# Rauchmelder_2_2A.net
KiCad netlist of a schematic drawn in EAGLE
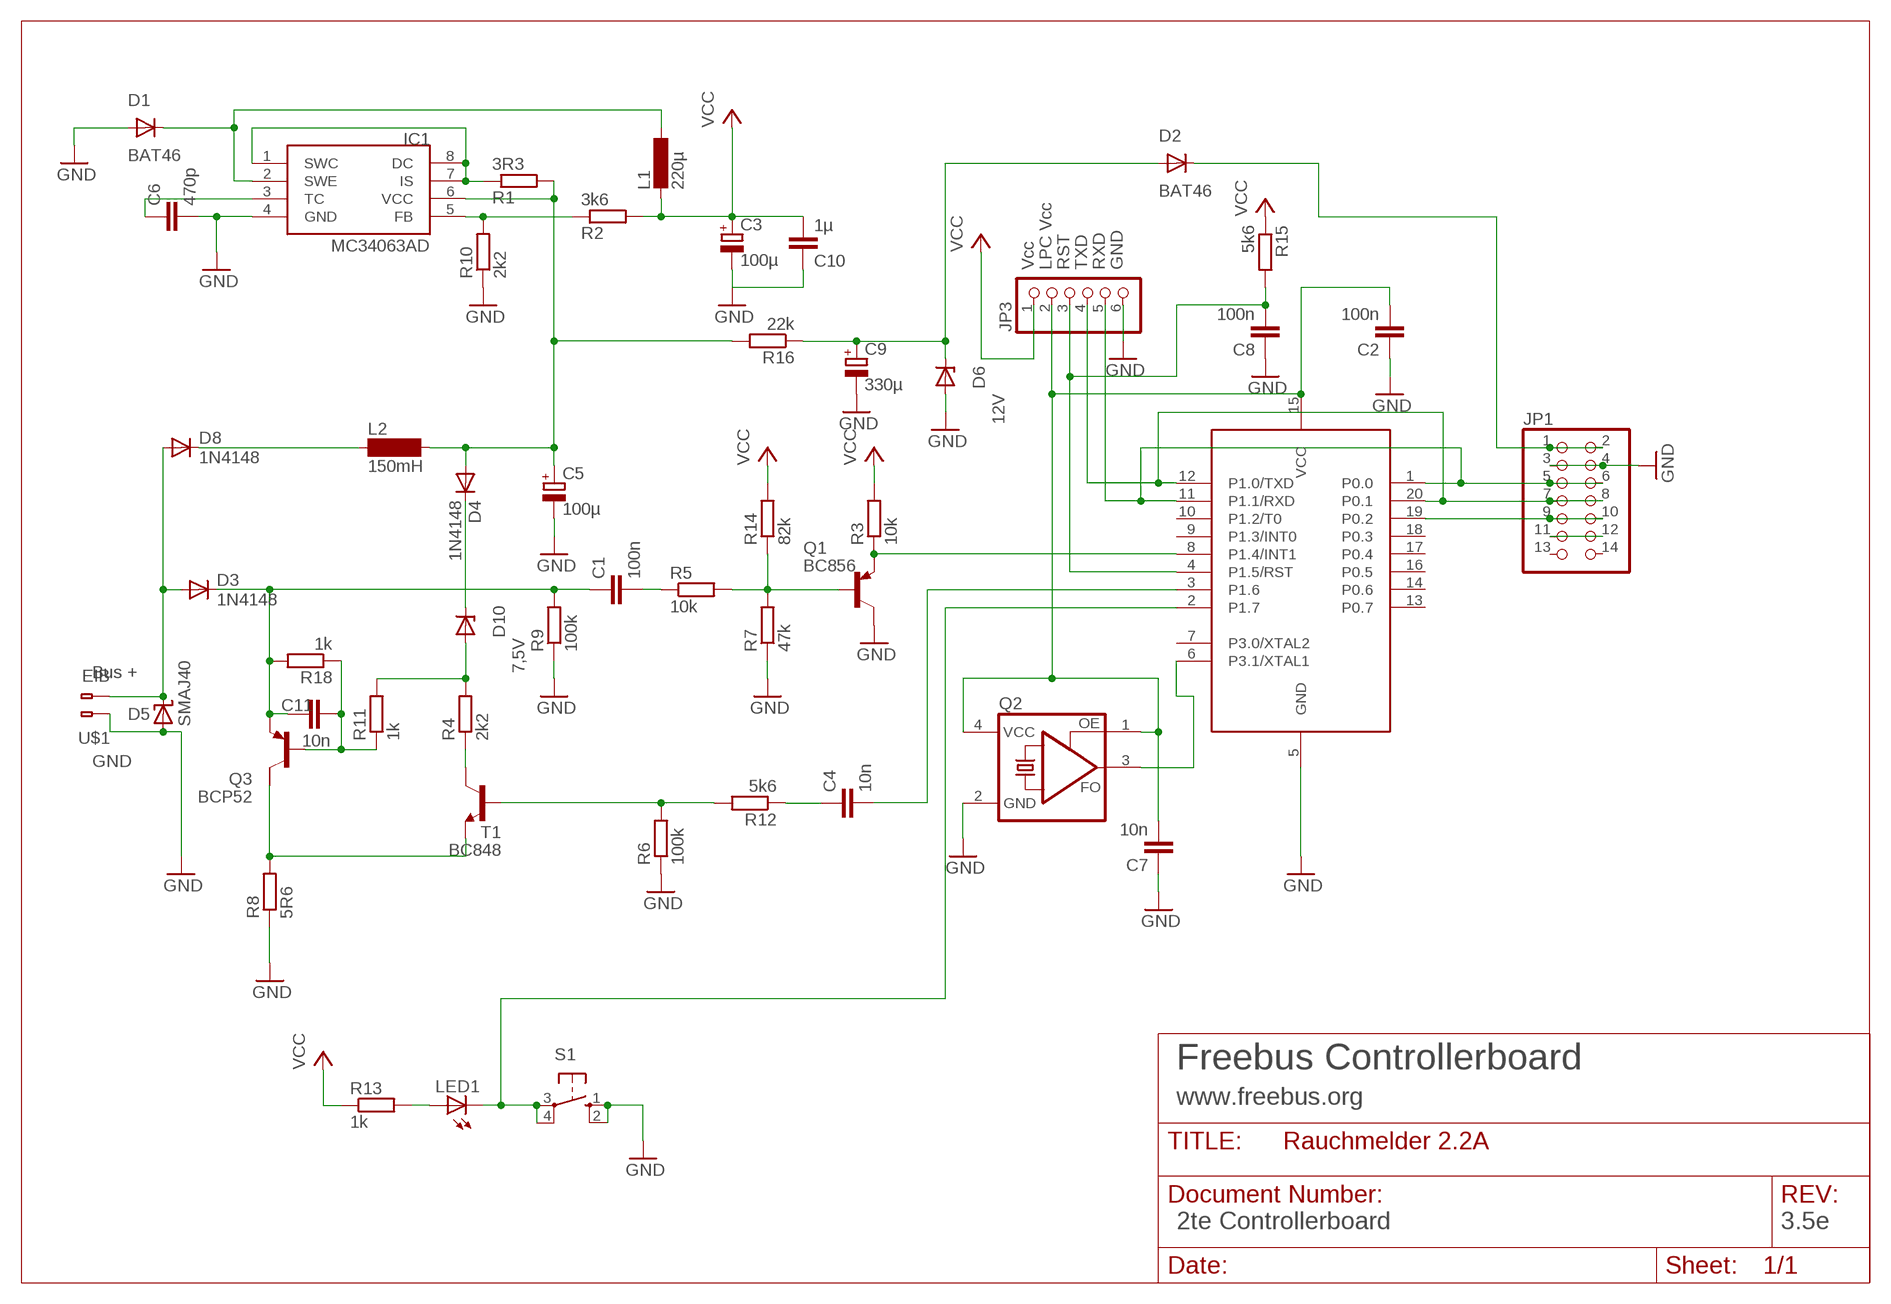
[diagram p0: schematic, sheet 1]

(export (version "E")
  (design (tool "Eeschema 10.0.6"))
  (components
    (comp (ref "C1")
      (value "100n")
      (footprint "eagle-import:C1206")
      (libsource (lib "eagle-import") (part "C-EUC1206"))
    )
    (comp (ref "C2")
      (value "100n")
      (footprint "eagle-import:C1206")
      (libsource (lib "eagle-import") (part "C-EUC1206"))
    )
    (comp (ref "C3")
      (value "100µ")
      (footprint "eagle-import:SANYO-OSCON_SMD_B6")
      (libsource (lib "eagle-import") (part "CPOL-EUSANYO_SMD_B6"))
    )
    (comp (ref "C4")
      (value "10n")
      (footprint "eagle-import:C1206")
      (libsource (lib "eagle-import") (part "C-EUC1206"))
    )
    (comp (ref "C5")
      (value "100µ")
      (footprint "eagle-import:SANYO-OSCON_SMD_C6")
      (libsource (lib "eagle-import") (part "CPOL-EUSANYO_SMD_C6"))
    )
    (comp (ref "C6")
      (value "470p")
      (footprint "eagle-import:C1206")
      (libsource (lib "eagle-import") (part "C-EUC1206"))
    )
    (comp (ref "C7")
      (value "10n")
      (footprint "eagle-import:C1206")
      (libsource (lib "eagle-import") (part "C-EUC1206"))
    )
    (comp (ref "C8")
      (value "100n")
      (footprint "eagle-import:C1206")
      (libsource (lib "eagle-import") (part "C-EUC1206"))
    )
    (comp (ref "C9")
      (value "330µ")
      (footprint "eagle-import:E3,5-8")
      (libsource (lib "eagle-import") (part "CPOL-EUE3.5-8"))
    )
    (comp (ref "C10")
      (value "1µ")
      (footprint "eagle-import:C1206")
      (libsource (lib "eagle-import") (part "C-EUC1206"))
    )
    (comp (ref "C11")
      (value "10n")
      (footprint "eagle-import:C1206")
      (libsource (lib "eagle-import") (part "C-EUC1206"))
    )
    (comp (ref "D1")
      (value "BAT46")
      (footprint "eagle-import:MINIMELF")
      (libsource (lib "eagle-import") (part "DIODE-MINIMELF"))
    )
    (comp (ref "D2")
      (value "BAT46")
      (footprint "eagle-import:MINIMELF")
      (libsource (lib "eagle-import") (part "DIODE-MINIMELF"))
    )
    (comp (ref "D3")
      (value "1N4148")
      (footprint "eagle-import:MINIMELF")
      (libsource (lib "eagle-import") (part "DIODE-MINIMELF"))
    )
    (comp (ref "D4")
      (value "1N4148")
      (footprint "eagle-import:MINIMELF")
      (libsource (lib "eagle-import") (part "DIODE-MINIMELF"))
    )
    (comp (ref "D5")
      (value "SMAJ40")
      (footprint "eagle-import:SMBJ")
      (libsource (lib "eagle-import") (part "SUPPRESSOR-SMBJ"))
    )
    (comp (ref "D6")
      (value "12V")
      (footprint "eagle-import:MINIMELF")
      (libsource (lib "eagle-import") (part "ZPD"))
    )
    (comp (ref "D8")
      (value "1N4148")
      (footprint "eagle-import:MINIMELF")
      (libsource (lib "eagle-import") (part "DIODE-MINIMELF"))
    )
    (comp (ref "D10")
      (value "7,5V")
      (footprint "eagle-import:MINIMELF")
      (libsource (lib "eagle-import") (part "ZPD"))
    )
    (comp (ref "IC1")
      (value "MC34063AD")
      (footprint "eagle-import:SOIC8")
      (libsource (lib "eagle-import") (part "MC34063AD"))
    )
    (comp (ref "IC3")
      (value "LPC922FDH")
      (footprint "eagle-import:TSSOP20")
      (libsource (lib "eagle-import") (part "LPC922FDH"))
    )
    (comp (ref "JP1")
      (value "PINHD-2X7")
      (footprint "eagle-import:2X07")
      (libsource (lib "eagle-import") (part "PINHD-2X7"))
    )
    (comp (ref "JP3")
      (value "PINHD-1X6")
      (footprint "eagle-import:1X06")
      (libsource (lib "eagle-import") (part "PINHD-1X6"))
    )
    (comp (ref "L1")
      (value "220µ")
      (footprint "eagle-import:0207_10")
      (libsource (lib "eagle-import") (part "L-EU0207/10"))
    )
    (comp (ref "L2")
      (value "150mH")
      (footprint "eagle-import:BS11")
      (libsource (lib "eagle-import") (part "BS11"))
    )
    (comp (ref "LED1")
      (value "LED3MM")
      (footprint "eagle-import:LED3MM")
      (libsource (lib "eagle-import") (part "LED3MM"))
    )
    (comp (ref "Q1")
      (value "BC856")
      (footprint "eagle-import:SOT23-BEC")
      (libsource (lib "eagle-import") (part "BC856SMDALT1"))
    )
    (comp (ref "Q2")
      (value "ASFL")
      (footprint "eagle-import:ASF")
      (libsource (lib "eagle-import") (part "ASFL"))
    )
    (comp (ref "Q3")
      (value "BCP52")
      (footprint "eagle-import:SOT223")
      (libsource (lib "eagle-import") (part "FZT753SMD"))
    )
    (comp (ref "R1")
      (value "3R3")
      (footprint "eagle-import:R1206")
      (libsource (lib "eagle-import") (part "R-EU_R1206"))
    )
    (comp (ref "R2")
      (value "3k6")
      (footprint "eagle-import:R1206")
      (libsource (lib "eagle-import") (part "R-EU_R1206"))
    )
    (comp (ref "R3")
      (value "10k")
      (footprint "eagle-import:R1206")
      (libsource (lib "eagle-import") (part "R-EU_R1206"))
    )
    (comp (ref "R4")
      (value "2k2")
      (footprint "eagle-import:R1206")
      (libsource (lib "eagle-import") (part "R-EU_R1206"))
    )
    (comp (ref "R5")
      (value "10k")
      (footprint "eagle-import:R1206")
      (libsource (lib "eagle-import") (part "R-EU_R1206"))
    )
    (comp (ref "R6")
      (value "100k")
      (footprint "eagle-import:R1206")
      (libsource (lib "eagle-import") (part "R-EU_R1206"))
    )
    (comp (ref "R7")
      (value "47k")
      (footprint "eagle-import:R1206")
      (libsource (lib "eagle-import") (part "R-EU_R1206"))
    )
    (comp (ref "R8")
      (value "5R6")
      (footprint "eagle-import:R1206")
      (libsource (lib "eagle-import") (part "R-EU_R1206"))
    )
    (comp (ref "R9")
      (value "100k")
      (footprint "eagle-import:R1206")
      (libsource (lib "eagle-import") (part "R-EU_R1206"))
    )
    (comp (ref "R10")
      (value "2k2")
      (footprint "eagle-import:R1206")
      (libsource (lib "eagle-import") (part "R-EU_R1206"))
    )
    (comp (ref "R11")
      (value "1k")
      (footprint "eagle-import:R1206")
      (libsource (lib "eagle-import") (part "R-EU_R1206"))
    )
    (comp (ref "R12")
      (value "5k6")
      (footprint "eagle-import:R1206")
      (libsource (lib "eagle-import") (part "R-EU_R1206"))
    )
    (comp (ref "R13")
      (value "1k")
      (footprint "eagle-import:R1206")
      (libsource (lib "eagle-import") (part "R-EU_R1206"))
    )
    (comp (ref "R14")
      (value "82k")
      (footprint "eagle-import:R1206")
      (libsource (lib "eagle-import") (part "R-EU_R1206"))
    )
    (comp (ref "R15")
      (value "5k6")
      (footprint "eagle-import:R1206")
      (libsource (lib "eagle-import") (part "R-EU_R1206"))
    )
    (comp (ref "R16")
      (value "22k")
      (footprint "eagle-import:R1206")
      (libsource (lib "eagle-import") (part "R-EU_R1206"))
    )
    (comp (ref "R18")
      (value "1k")
      (footprint "eagle-import:R1206")
      (libsource (lib "eagle-import") (part "R-EU_R1206"))
    )
    (comp (ref "S1")
      (value "10-XX")
      (footprint "eagle-import:B3F-10XX")
      (libsource (lib "eagle-import") (part "10-XX"))
    )
    (comp (ref "T1")
      (value "BC848")
      (footprint "eagle-import:SOT23")
      (libsource (lib "eagle-import") (part "BC848"))
    )
    (comp (ref "U$1")
      (value "EIB")
      (footprint "eagle-import:BUSKLEMME243-724")
      (libsource (lib "eagle-import") (part "EIB"))
    )
  )
  (nets
    (net (code "1") (name "GND") (class "Default")
      (node (ref "C10") (pin "1") (pinfunction "1_1") (pintype "passive"))
      (node (ref "C2") (pin "1") (pinfunction "1_1") (pintype "passive"))
      (node (ref "C3") (pin "-") (pinfunction "-_-") (pintype "passive"))
      (node (ref "C5") (pin "-") (pinfunction "-_-") (pintype "passive"))
      (node (ref "C6") (pin "2") (pinfunction "2_2") (pintype "passive"))
      (node (ref "C7") (pin "1") (pinfunction "1_1") (pintype "passive"))
      (node (ref "C8") (pin "1") (pinfunction "1_1") (pintype "passive"))
      (node (ref "C9") (pin "-") (pinfunction "-_-") (pintype "passive"))
      (node (ref "D1") (pin "A") (pinfunction "A_A") (pintype "passive"))
      (node (ref "D5") (pin "A") (pinfunction "A_A") (pintype "passive"))
      (node (ref "D6") (pin "A") (pinfunction "A_A") (pintype "passive"))
      (node (ref "IC1") (pin "4") (pinfunction "GND_4") (pintype "passive"))
      (node (ref "IC3") (pin "5") (pinfunction "GND_5") (pintype "bidirectional"))
      (node (ref "JP1") (pin "3") (pinfunction "3_3") (pintype "passive"))
      (node (ref "JP1") (pin "4") (pinfunction "4_4") (pintype "passive"))
      (node (ref "JP3") (pin "6") (pinfunction "6_6") (pintype "passive"))
      (node (ref "Q1") (pin "C") (pinfunction "C_C") (pintype "passive"))
      (node (ref "Q2") (pin "2") (pinfunction "GND_2") (pintype "power_in"))
      (node (ref "R10") (pin "1") (pinfunction "1_1") (pintype "passive"))
      (node (ref "R6") (pin "1") (pinfunction "1_1") (pintype "passive"))
      (node (ref "R7") (pin "1") (pinfunction "1_1") (pintype "passive"))
      (node (ref "R8") (pin "1") (pinfunction "1_1") (pintype "passive"))
      (node (ref "R9") (pin "1") (pinfunction "1_1") (pintype "passive"))
      (node (ref "S1") (pin "1") (pinfunction "S_1") (pintype "passive"))
      (node (ref "S1") (pin "2") (pinfunction "S1_2") (pintype "passive"))
      (node (ref "U$1") (pin "1") (pinfunction "B-1_1") (pintype "passive"))
    )
    (net (code "2") (name "Net-(C1-Pad2)") (class "Default")
      (node (ref "C1") (pin "2") (pinfunction "2_2") (pintype "passive"))
      (node (ref "R5") (pin "1") (pinfunction "1_1") (pintype "passive"))
    )
    (net (code "3") (name "Net-(C4-Pad1)") (class "Default")
      (node (ref "C4") (pin "1") (pinfunction "1_1") (pintype "passive"))
      (node (ref "R12") (pin "1") (pinfunction "1_1") (pintype "passive"))
    )
    (net (code "4") (name "Net-(C9-Pad+)") (class "Default")
      (node (ref "C9") (pin "+") (pinfunction "+_+") (pintype "passive"))
      (node (ref "D2") (pin "A") (pinfunction "A_A") (pintype "passive"))
      (node (ref "D6") (pin "C") (pinfunction "C_C") (pintype "passive"))
      (node (ref "R16") (pin "1") (pinfunction "1_1") (pintype "passive"))
    )
    (net (code "5") (name "Net-(D2-PadC)") (class "Default")
      (node (ref "D2") (pin "C") (pinfunction "C_C") (pintype "passive"))
      (node (ref "JP1") (pin "1") (pinfunction "1_1") (pintype "passive"))
      (node (ref "JP1") (pin "2") (pinfunction "2_2") (pintype "passive"))
    )
    (net (code "6") (name "Net-(D8-PadC)") (class "Default")
      (node (ref "D8") (pin "C") (pinfunction "C_C") (pintype "passive"))
      (node (ref "L2") (pin "1") (pinfunction "1_1") (pintype "passive"))
    )
    (net (code "7") (name "Net-(D10-PadA)") (class "Default")
      (node (ref "D10") (pin "A") (pinfunction "A_A") (pintype "passive"))
      (node (ref "R11") (pin "2") (pinfunction "2_2") (pintype "passive"))
      (node (ref "R4") (pin "2") (pinfunction "2_2") (pintype "passive"))
    )
    (net (code "8") (name "Net-(D10-PadC)") (class "Default")
      (node (ref "D10") (pin "C") (pinfunction "C_C") (pintype "passive"))
      (node (ref "D4") (pin "C") (pinfunction "C_C") (pintype "passive"))
    )
    (net (code "9") (name "Net-(IC1-DC)") (class "Default")
      (node (ref "IC1") (pin "1") (pinfunction "SWC_1") (pintype "passive"))
      (node (ref "IC1") (pin "7") (pinfunction "IS_7") (pintype "passive"))
      (node (ref "IC1") (pin "8") (pinfunction "DC_8") (pintype "passive"))
      (node (ref "R1") (pin "1") (pinfunction "1_1") (pintype "passive"))
    )
    (net (code "10") (name "Net-(IC1-FB)") (class "Default")
      (node (ref "IC1") (pin "5") (pinfunction "FB_5") (pintype "passive"))
      (node (ref "R10") (pin "2") (pinfunction "2_2") (pintype "passive"))
      (node (ref "R2") (pin "1") (pinfunction "1_1") (pintype "passive"))
    )
    (net (code "11") (name "Net-(IC1-SWE)") (class "Default")
      (node (ref "D1") (pin "C") (pinfunction "C_C") (pintype "passive"))
      (node (ref "IC1") (pin "2") (pinfunction "SWE_2") (pintype "passive"))
      (node (ref "L1") (pin "1") (pinfunction "1_1") (pintype "passive"))
    )
    (net (code "12") (name "Net-(IC1-TC)") (class "Default")
      (node (ref "C6") (pin "1") (pinfunction "1_1") (pintype "passive"))
      (node (ref "IC1") (pin "3") (pinfunction "TC_3") (pintype "passive"))
    )
    (net (code "13") (name "Net-(IC1-VCC)") (class "Default")
      (node (ref "C5") (pin "+") (pinfunction "+_+") (pintype "passive"))
      (node (ref "D4") (pin "A") (pinfunction "A_A") (pintype "passive"))
      (node (ref "IC1") (pin "6") (pinfunction "VCC_6") (pintype "passive"))
      (node (ref "L2") (pin "2") (pinfunction "2_2") (pintype "passive"))
      (node (ref "R1") (pin "2") (pinfunction "2_2") (pintype "passive"))
      (node (ref "R16") (pin "2") (pinfunction "2_2") (pintype "passive"))
    )
    (net (code "14") (name "Net-(IC3-P0.0)") (class "Default")
      (node (ref "IC3") (pin "1") (pinfunction "P0.0_1") (pintype "bidirectional"))
      (node (ref "IC3") (pin "11") (pinfunction "P1.1/RXD_11") (pintype "bidirectional"))
      (node (ref "JP1") (pin "5") (pinfunction "5_5") (pintype "passive"))
      (node (ref "JP1") (pin "6") (pinfunction "6_6") (pintype "passive"))
      (node (ref "JP3") (pin "5") (pinfunction "5_5") (pintype "passive"))
    )
    (net (code "15") (name "Net-(IC3-P0.1)") (class "Default")
      (node (ref "IC3") (pin "12") (pinfunction "P1.0/TXD_12") (pintype "bidirectional"))
      (node (ref "IC3") (pin "20") (pinfunction "P0.1_20") (pintype "bidirectional"))
      (node (ref "JP1") (pin "7") (pinfunction "7_7") (pintype "passive"))
      (node (ref "JP1") (pin "8") (pinfunction "8_8") (pintype "passive"))
      (node (ref "JP3") (pin "4") (pinfunction "4_4") (pintype "passive"))
    )
    (net (code "16") (name "Net-(IC3-P0.2)") (class "Default")
      (node (ref "IC3") (pin "19") (pinfunction "P0.2_19") (pintype "bidirectional"))
      (node (ref "JP1") (pin "10") (pinfunction "10_10") (pintype "passive"))
      (node (ref "JP1") (pin "9") (pinfunction "9_9") (pintype "passive"))
    )
    (net (code "17") (name "Net-(IC3-P1.4{slash}INT1)") (class "Default")
      (node (ref "IC3") (pin "8") (pinfunction "P1.4/INT1_8") (pintype "bidirectional"))
      (node (ref "Q1") (pin "E") (pinfunction "E_E") (pintype "passive"))
      (node (ref "R3") (pin "1") (pinfunction "1_1") (pintype "passive"))
    )
    (net (code "18") (name "Net-(IC3-P1.5{slash}RST)") (class "Default")
      (node (ref "C8") (pin "2") (pinfunction "2_2") (pintype "passive"))
      (node (ref "IC3") (pin "4") (pinfunction "P1.5/RST_4") (pintype "bidirectional"))
      (node (ref "JP3") (pin "3") (pinfunction "3_3") (pintype "passive"))
      (node (ref "R15") (pin "2") (pinfunction "2_2") (pintype "passive"))
    )
    (net (code "19") (name "Net-(IC3-P1.6)") (class "Default")
      (node (ref "C4") (pin "2") (pinfunction "2_2") (pintype "passive"))
      (node (ref "IC3") (pin "3") (pinfunction "P1.6_3") (pintype "bidirectional"))
    )
    (net (code "20") (name "Net-(IC3-P1.7)") (class "Default")
      (node (ref "IC3") (pin "2") (pinfunction "P1.7_2") (pintype "bidirectional"))
      (node (ref "LED1") (pin "K") (pinfunction "C_K") (pintype "passive"))
      (node (ref "S1") (pin "3") (pinfunction "P_3") (pintype "passive"))
      (node (ref "S1") (pin "4") (pinfunction "P1_4") (pintype "passive"))
    )
    (net (code "21") (name "Net-(IC3-P3.1{slash}XTAL1)") (class "Default")
      (node (ref "IC3") (pin "6") (pinfunction "P3.1/XTAL1_6") (pintype "bidirectional"))
      (node (ref "Q2") (pin "3") (pinfunction "FO_3") (pintype "output"))
    )
    (net (code "22") (name "Net-(IC3-VCC)") (class "Default")
      (node (ref "C2") (pin "2") (pinfunction "2_2") (pintype "passive"))
      (node (ref "C7") (pin "2") (pinfunction "2_2") (pintype "passive"))
      (node (ref "IC3") (pin "15") (pinfunction "VCC_15") (pintype "bidirectional"))
      (node (ref "JP3") (pin "2") (pinfunction "2_2") (pintype "passive"))
      (node (ref "Q2") (pin "1") (pinfunction "OE_1") (pintype "input"))
      (node (ref "Q2") (pin "4") (pinfunction "VCC_4") (pintype "power_in"))
    )
    (net (code "23") (name "Net-(JP1-Pad11)") (class "Default")
      (node (ref "JP1") (pin "11") (pinfunction "11_11") (pintype "passive"))
      (node (ref "JP1") (pin "12") (pinfunction "12_12") (pintype "passive"))
    )
    (net (code "24") (name "Net-(LED1-PadA)") (class "Default")
      (node (ref "LED1") (pin "A") (pinfunction "A_A") (pintype "passive"))
      (node (ref "R13") (pin "2") (pinfunction "2_2") (pintype "passive"))
    )
    (net (code "25") (name "Net-(Q1-PadB)") (class "Default")
      (node (ref "Q1") (pin "B") (pinfunction "B_B") (pintype "passive"))
      (node (ref "R14") (pin "1") (pinfunction "1_1") (pintype "passive"))
      (node (ref "R5") (pin "2") (pinfunction "2_2") (pintype "passive"))
      (node (ref "R7") (pin "2") (pinfunction "2_2") (pintype "passive"))
    )
    (net (code "26") (name "Net-(Q3-B)") (class "Default")
      (node (ref "C11") (pin "2") (pinfunction "2_2") (pintype "passive"))
      (node (ref "Q3") (pin "1") (pinfunction "B_1") (pintype "passive"))
      (node (ref "R11") (pin "1") (pinfunction "1_1") (pintype "passive"))
      (node (ref "R18") (pin "1") (pinfunction "1_1") (pintype "passive"))
    )
    (net (code "27") (name "Net-(Q3-C)") (class "Default")
      (node (ref "Q3") (pin "2") (pinfunction "C_2") (pintype "passive"))
      (node (ref "R8") (pin "2") (pinfunction "2_2") (pintype "passive"))
      (node (ref "T1") (pin "2") (pinfunction "E_2") (pintype "passive"))
    )
    (net (code "28") (name "Net-(Q3-E)") (class "Default")
      (node (ref "C1") (pin "1") (pinfunction "1_1") (pintype "passive"))
      (node (ref "C11") (pin "1") (pinfunction "1_1") (pintype "passive"))
      (node (ref "D3") (pin "C") (pinfunction "C_C") (pintype "passive"))
      (node (ref "Q3") (pin "3") (pinfunction "E_3") (pintype "passive"))
      (node (ref "R18") (pin "2") (pinfunction "2_2") (pintype "passive"))
      (node (ref "R9") (pin "2") (pinfunction "2_2") (pintype "passive"))
    )
    (net (code "29") (name "Net-(T1-B)") (class "Default")
      (node (ref "R12") (pin "2") (pinfunction "2_2") (pintype "passive"))
      (node (ref "R6") (pin "2") (pinfunction "2_2") (pintype "passive"))
      (node (ref "T1") (pin "1") (pinfunction "B_1") (pintype "passive"))
    )
    (net (code "30") (name "Net-(T1-C)") (class "Default")
      (node (ref "R4") (pin "1") (pinfunction "1_1") (pintype "passive"))
      (node (ref "T1") (pin "3") (pinfunction "C_3") (pintype "passive"))
    )
    (net (code "31") (name "Net-(U$1-B-2)") (class "Default")
      (node (ref "D3") (pin "A") (pinfunction "A_A") (pintype "passive"))
      (node (ref "D5") (pin "C") (pinfunction "C_C") (pintype "passive"))
      (node (ref "D8") (pin "A") (pinfunction "A_A") (pintype "passive"))
      (node (ref "U$1") (pin "2") (pinfunction "B-2_2") (pintype "passive"))
    )
    (net (code "32") (name "VCC") (class "Default")
      (node (ref "C10") (pin "2") (pinfunction "2_2") (pintype "passive"))
      (node (ref "C3") (pin "+") (pinfunction "+_+") (pintype "passive"))
      (node (ref "JP3") (pin "1") (pinfunction "1_1") (pintype "passive"))
      (node (ref "L1") (pin "2") (pinfunction "2_2") (pintype "passive"))
      (node (ref "R13") (pin "1") (pinfunction "1_1") (pintype "passive"))
      (node (ref "R14") (pin "2") (pinfunction "2_2") (pintype "passive"))
      (node (ref "R15") (pin "1") (pinfunction "1_1") (pintype "passive"))
      (node (ref "R2") (pin "2") (pinfunction "2_2") (pintype "passive"))
      (node (ref "R3") (pin "2") (pinfunction "2_2") (pintype "passive"))
    )
    (net (code "33") (name "unconnected-(IC3-P0.3-Pad18)") (class "Default")
      (node (ref "IC3") (pin "18") (pinfunction "P0.3_18") (pintype "bidirectional"))
    )
    (net (code "34") (name "unconnected-(IC3-P0.4-Pad17)") (class "Default")
      (node (ref "IC3") (pin "17") (pinfunction "P0.4_17") (pintype "bidirectional"))
    )
    (net (code "35") (name "unconnected-(IC3-P0.5-Pad16)") (class "Default")
      (node (ref "IC3") (pin "16") (pinfunction "P0.5_16") (pintype "bidirectional"))
    )
    (net (code "36") (name "unconnected-(IC3-P0.6-Pad14)") (class "Default")
      (node (ref "IC3") (pin "14") (pinfunction "P0.6_14") (pintype "bidirectional"))
    )
    (net (code "37") (name "unconnected-(IC3-P0.7-Pad13)") (class "Default")
      (node (ref "IC3") (pin "13") (pinfunction "P0.7_13") (pintype "bidirectional"))
    )
    (net (code "38") (name "unconnected-(IC3-P1.2{slash}T0-Pad10)") (class "Default")
      (node (ref "IC3") (pin "10") (pinfunction "P1.2/T0_10") (pintype "bidirectional"))
    )
    (net (code "39") (name "unconnected-(IC3-P1.3{slash}INT0-Pad9)") (class "Default")
      (node (ref "IC3") (pin "9") (pinfunction "P1.3/INT0_9") (pintype "bidirectional"))
    )
    (net (code "40") (name "unconnected-(IC3-P3.0{slash}XTAL2-Pad7)") (class "Default")
      (node (ref "IC3") (pin "7") (pinfunction "P3.0/XTAL2_7") (pintype "bidirectional"))
    )
    (net (code "41") (name "unconnected-(JP1-Pad13)") (class "Default")
      (node (ref "JP1") (pin "13") (pinfunction "13_13") (pintype "passive"))
    )
    (net (code "42") (name "unconnected-(JP1-Pad14)") (class "Default")
      (node (ref "JP1") (pin "14") (pinfunction "14_14") (pintype "passive"))
    )
    (net (code "43") (name "unconnected-(Q3-C{slash}-Pad4)") (class "Default")
      (node (ref "Q3") (pin "4") (pinfunction "C/_4") (pintype "passive"))
    )
  )
)
